# fatshark58.net
KiCad netlist of a schematic drawn in EAGLE
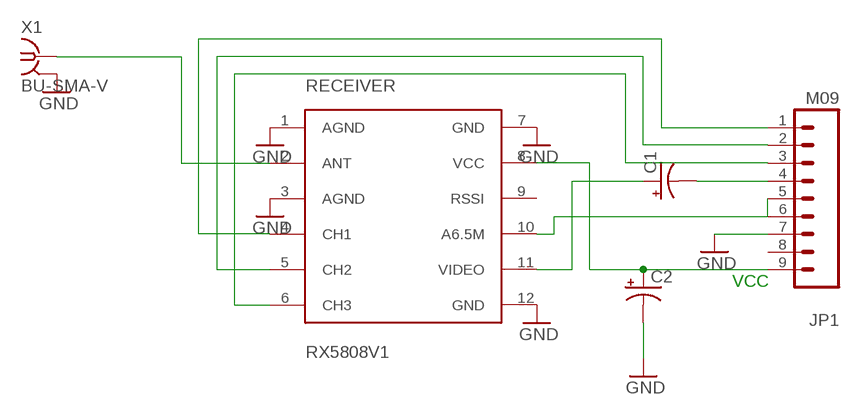
[diagram p0: schematic, sheet 1]

(export (version "E")
  (design (tool "Eeschema 10.0.6"))
  (components
    (comp (ref "C1")
      (value "CAP_POL7343")
      (footprint "eagle-import:EIA7343")
      (libsource (lib "eagle-import") (part "CAP_POL7343"))
    )
    (comp (ref "C2")
      (value "CAP_POL7343")
      (footprint "eagle-import:EIA7343")
      (libsource (lib "eagle-import") (part "CAP_POL7343"))
    )
    (comp (ref "JP1")
      (value "M09")
      (footprint "eagle-import:1X09")
      (libsource (lib "eagle-import") (part "M09"))
    )
    (comp (ref "RECEIVER")
      (value "RX5808V1")
      (footprint "eagle-import:RX5808")
      (libsource (lib "eagle-import") (part "RX5808V1"))
    )
    (comp (ref "X1")
      (value "BU-SMA-V")
      (footprint "eagle-import:BU-SMA-V")
      (libsource (lib "eagle-import") (part "BU-SMA-V"))
    )
  )
  (nets
    (net (code "1") (name "GND") (class "Default")
      (node (ref "C2") (pin "C") (pinfunction "-_C") (pintype "passive"))
      (node (ref "JP1") (pin "7") (pinfunction "7_7") (pintype "passive"))
      (node (ref "RECEIVER") (pin "1") (pinfunction "AGND_1") (pintype "input"))
      (node (ref "RECEIVER") (pin "12") (pinfunction "GND_12") (pintype "power_in"))
      (node (ref "RECEIVER") (pin "3") (pinfunction "AGND_3") (pintype "input"))
      (node (ref "RECEIVER") (pin "7") (pinfunction "GND_7") (pintype "power_in"))
      (node (ref "X1") (pin "2") (pinfunction "2_2") (pintype "passive"))
      (node (ref "X1") (pin "3") (pinfunction "2_3") (pintype "passive"))
      (node (ref "X1") (pin "4") (pinfunction "2_4") (pintype "passive"))
      (node (ref "X1") (pin "5") (pinfunction "2_5") (pintype "passive"))
    )
    (net (code "2") (name "Net-(C1-+)") (class "Default")
      (node (ref "C1") (pin "A") (pinfunction "+_A") (pintype "passive"))
      (node (ref "RECEIVER") (pin "11") (pinfunction "VIDEO_11") (pintype "output"))
    )
    (net (code "3") (name "Net-(C1--)") (class "Default")
      (node (ref "C1") (pin "C") (pinfunction "-_C") (pintype "passive"))
      (node (ref "JP1") (pin "4") (pinfunction "4_4") (pintype "passive"))
    )
    (net (code "4") (name "Net-(C2-+)") (class "Default")
      (node (ref "C2") (pin "A") (pinfunction "+_A") (pintype "passive"))
      (node (ref "JP1") (pin "9") (pinfunction "9_9") (pintype "passive"))
      (node (ref "RECEIVER") (pin "8") (pinfunction "VCC_8") (pintype "power_in"))
    )
    (net (code "5") (name "Net-(RECEIVER-A6.5M)") (class "Default")
      (node (ref "JP1") (pin "5") (pinfunction "5_5") (pintype "passive"))
      (node (ref "JP1") (pin "6") (pinfunction "6_6") (pintype "passive"))
      (node (ref "RECEIVER") (pin "10") (pinfunction "A6.5M_10") (pintype "output"))
    )
    (net (code "6") (name "Net-(RECEIVER-ANT)") (class "Default")
      (node (ref "RECEIVER") (pin "2") (pinfunction "ANT_2") (pintype "input"))
      (node (ref "X1") (pin "1") (pinfunction "1_1") (pintype "passive"))
    )
    (net (code "7") (name "Net-(RECEIVER-CH1)") (class "Default")
      (node (ref "JP1") (pin "1") (pinfunction "1_1") (pintype "passive"))
      (node (ref "RECEIVER") (pin "4") (pinfunction "CH1_4") (pintype "input"))
    )
    (net (code "8") (name "Net-(RECEIVER-CH2)") (class "Default")
      (node (ref "JP1") (pin "2") (pinfunction "2_2") (pintype "passive"))
      (node (ref "RECEIVER") (pin "5") (pinfunction "CH2_5") (pintype "input"))
    )
    (net (code "9") (name "Net-(RECEIVER-CH3)") (class "Default")
      (node (ref "JP1") (pin "3") (pinfunction "3_3") (pintype "passive"))
      (node (ref "RECEIVER") (pin "6") (pinfunction "CH3_6") (pintype "input"))
    )
    (net (code "10") (name "unconnected-(JP1-Pad8)") (class "Default")
      (node (ref "JP1") (pin "8") (pinfunction "8_8") (pintype "passive"))
    )
    (net (code "11") (name "unconnected-(RECEIVER-RSSI-Pad9)") (class "Default")
      (node (ref "RECEIVER") (pin "9") (pinfunction "RSSI_9") (pintype "output"))
    )
  )
)
